# PCB-Main.net
KiCad netlist of a schematic drawn in EAGLE
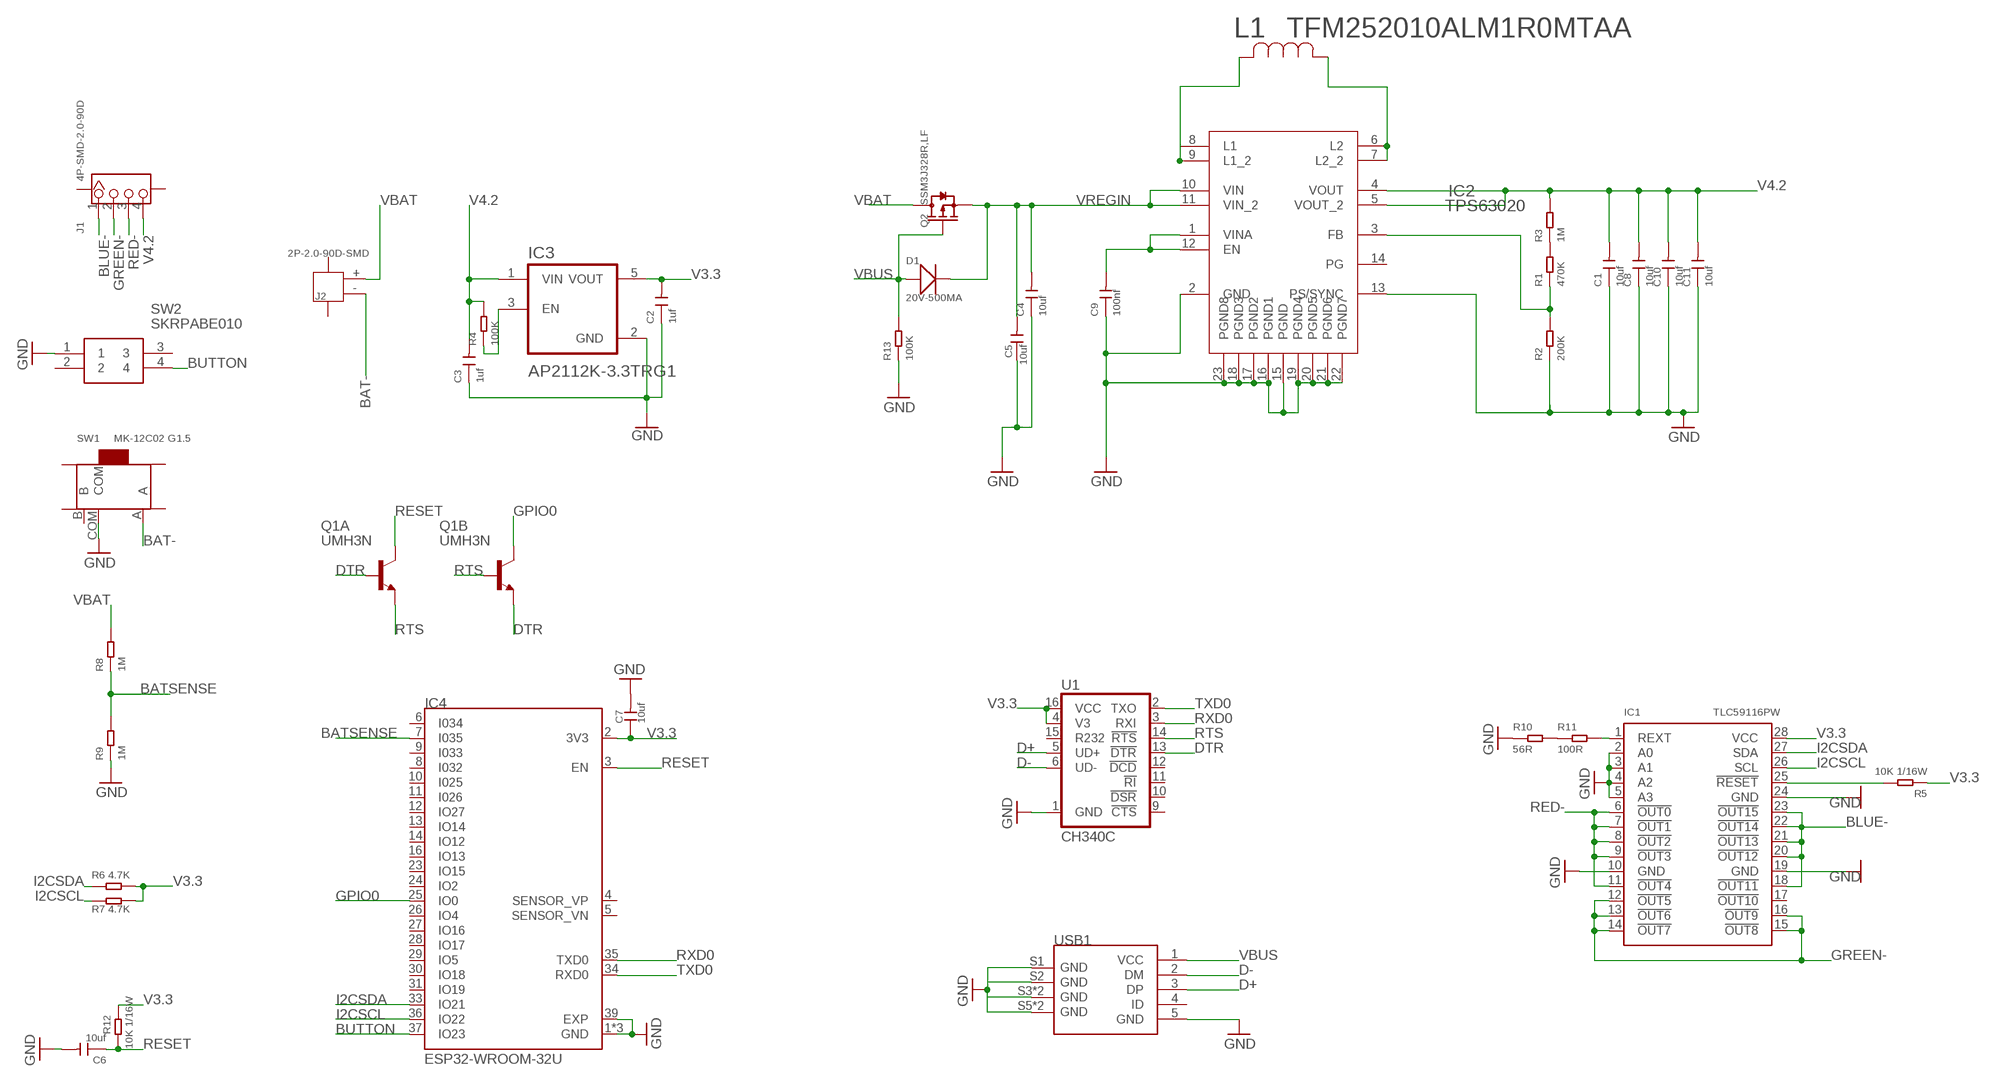
[diagram p0: schematic, sheet 1]

(export (version "E")
  (design (tool "Eeschema 10.0.6"))
  (components
    (comp (ref "C1")
      (value "10uf")
      (footprint "eagle-import:C0402")
      (fields (field (name "MPN") "CC0402MRX5R5BB106"))
      (libsource (lib "eagle-import") (part "CERAMIC-10UF-6.3V-20%-X5R(0402)"))
    )
    (comp (ref "C2")
      (value "1uf")
      (footprint "eagle-import:C0402")
      (fields (field (name "MPN") "CC0402KRX5R6BB105"))
      (libsource (lib "eagle-import") (part "CERAMIC-1UF-10V-10%-X5R(0402)"))
    )
    (comp (ref "C3")
      (value "1uf")
      (footprint "eagle-import:C0402")
      (fields (field (name "MPN") "CC0402KRX5R6BB105"))
      (libsource (lib "eagle-import") (part "CERAMIC-1UF-10V-10%-X5R(0402)"))
    )
    (comp (ref "C4")
      (value "10uf")
      (footprint "eagle-import:C0402")
      (fields (field (name "MPN") "CC0402MRX5R5BB106"))
      (libsource (lib "eagle-import") (part "CERAMIC-10UF-6.3V-20%-X5R(0402)"))
    )
    (comp (ref "C5")
      (value "10uf")
      (footprint "eagle-import:C0402")
      (fields (field (name "MPN") "CC0402MRX5R5BB106"))
      (libsource (lib "eagle-import") (part "CERAMIC-10UF-6.3V-20%-X5R(0402)"))
    )
    (comp (ref "C6")
      (value "10uf")
      (footprint "eagle-import:C0402")
      (fields (field (name "MPN") "CC0402MRX5R5BB106"))
      (libsource (lib "eagle-import") (part "CERAMIC-10UF-6.3V-20%-X5R(0402)"))
    )
    (comp (ref "C7")
      (value "10uf")
      (footprint "eagle-import:C0402")
      (fields (field (name "MPN") "CC0402MRX5R5BB106"))
      (libsource (lib "eagle-import") (part "CERAMIC-10UF-6.3V-20%-X5R(0402)"))
    )
    (comp (ref "C8")
      (value "10uf")
      (footprint "eagle-import:C0402")
      (fields (field (name "MPN") "CC0402MRX5R5BB106"))
      (libsource (lib "eagle-import") (part "CERAMIC-10UF-6.3V-20%-X5R(0402)"))
    )
    (comp (ref "C9")
      (value "100nf")
      (footprint "eagle-import:C0402")
      (fields (field (name "MPN") "CC0402KRX7R8BB104"))
      (libsource (lib "eagle-import") (part "CERAMIC-100NF-25V-10%-X7R(0402)"))
    )
    (comp (ref "C10")
      (value "10uf")
      (footprint "eagle-import:C0402")
      (fields (field (name "MPN") "CC0402MRX5R5BB106"))
      (libsource (lib "eagle-import") (part "CERAMIC-10UF-6.3V-20%-X5R(0402)"))
    )
    (comp (ref "C11")
      (value "10uf")
      (footprint "eagle-import:C0402")
      (fields (field (name "MPN") "CC0402MRX5R5BB106"))
      (libsource (lib "eagle-import") (part "CERAMIC-10UF-6.3V-20%-X5R(0402)"))
    )
    (comp (ref "D1")
      (value "20V-500MA")
      (footprint "eagle-import:SOD-123")
      (fields (field (name "MPN") "SS0520-7-F"))
      (libsource (lib "eagle-import") (part "SMD-DIODE-SCHOTTKY-20V-500MA(SOD-123)"))
    )
    (comp (ref "IC1")
      (value "TLC59116PW")
      (footprint "eagle-import:PW_R-PDSO-G28")
      (fields (field (name "MPN") "TLC59116IPWR"))
      (libsource (lib "eagle-import") (part "TLC59116PW"))
    )
    (comp (ref "IC2")
      (value "TPS63020")
      (footprint "eagle-import:QFN14-3X4MM")
      (fields (field (name "MF") "Texas Instruments") (field (name "MPN") "TPS63020DSJR"))
      (libsource (lib "eagle-import") (part "TPS63020"))
    )
    (comp (ref "IC3")
      (value "AP2112K-3.3TRG1")
      (footprint "eagle-import:SOT95P285X140-5N")
      (fields (field (name "MF") "Diodes Inc."))
      (libsource (lib "eagle-import") (part "AP2112K-3.3TRG1"))
    )
    (comp (ref "IC4")
      (value "ESP32-WROOM-32U")
      (footprint "eagle-import:XCVR_ESP32-WROOM-32U")
      (fields (field (name "MF") "Espressif Systems"))
      (libsource (lib "eagle-import") (part "ESP32-WROOM-32UNOSD"))
    )
    (comp (ref "J1")
      (value "4P-SMD-2.0-90D")
      (footprint "eagle-import:HW4-SMD-2.0-90D")
      (libsource (lib "eagle-import") (part "GROVE-CONNECTOR-SMD-90D(4+2P-2.0)"))
    )
    (comp (ref "J2")
      (value "2P-2.0-90D-SMD")
      (footprint "eagle-import:HW2-SMD-2.0-90D")
      (libsource (lib "eagle-import") (part "CONN-HEADER-SMD-PH-SIDE-(2P-2.0MM)"))
    )
    (comp (ref "L1")
      (value "TFM252010ALM1R0MTAA")
      (footprint "eagle-import:IND_1008")
      (libsource (lib "eagle-import") (part "TFM252010ALM1R0MTAA"))
    )
    (comp (ref "Q1")
      (value "UMH3N")
      (footprint "eagle-import:UMT6")
      (fields (field (name "MPN") "UMH3NTN"))
      (libsource (lib "eagle-import") (part "UMH3N"))
    )
    (comp (ref "Q2")
      (value "SSM3J328R,LF")
      (footprint "eagle-import:SOT-23")
      (libsource (lib "eagle-import") (part "SMD-MOSFET-P-CH-20V-6A-SSM3J328R(SOT-23)"))
    )
    (comp (ref "R1")
      (value "470K")
      (footprint "eagle-import:R0402")
      (fields (field (name "MPN") "RC0402FR-07470KL"))
      (libsource (lib "eagle-import") (part "SMD-RES-470K-1%-1/16W(0402)"))
    )
    (comp (ref "R2")
      (value "200K")
      (footprint "eagle-import:R0402")
      (fields (field (name "MPN") "RC0402JR-070RL"))
      (libsource (lib "eagle-import") (part "SMD-RES-200K-5%-1/16W(0402)"))
    )
    (comp (ref "R3")
      (value "1M")
      (footprint "eagle-import:R0402")
      (fields (field (name "MPN") "RC0402FR-071ML"))
      (libsource (lib "eagle-import") (part "SMD-RES-1M-1%-1/16W(0402)"))
    )
    (comp (ref "R4")
      (value "100K")
      (footprint "eagle-import:R0402")
      (fields (field (name "MPN") "RC0402FR-07100KL"))
      (libsource (lib "eagle-import") (part "SMD-RES-100K-1%-1/16W(0402)"))
    )
    (comp (ref "R5")
      (value "10K 1/16W")
      (footprint "eagle-import:R0402")
      (fields (field (name "MPN") "RC0402FR-0710KL"))
      (libsource (lib "eagle-import") (part "SMD-RES-10K-1%-1/16W(0402)"))
    )
    (comp (ref "R6")
      (value "4.7K")
      (footprint "eagle-import:R0402")
      (fields (field (name "MPN") "RC0402JR-074K7L"))
      (libsource (lib "eagle-import") (part "SMD-RES-4.7K-5%-1/16W(0402)"))
    )
    (comp (ref "R7")
      (value "4.7K")
      (footprint "eagle-import:R0402")
      (fields (field (name "MPN") "RC0402JR-074K7L"))
      (libsource (lib "eagle-import") (part "SMD-RES-4.7K-5%-1/16W(0402)"))
    )
    (comp (ref "R8")
      (value "1M")
      (footprint "eagle-import:R0402")
      (fields (field (name "MPN") "RC0402FR-071ML"))
      (libsource (lib "eagle-import") (part "SMD-RES-1M-1%-1/16W(0402)"))
    )
    (comp (ref "R9")
      (value "1M")
      (footprint "eagle-import:R0402")
      (fields (field (name "MPN") "RC0402FR-071ML"))
      (libsource (lib "eagle-import") (part "SMD-RES-1M-1%-1/16W(0402)"))
    )
    (comp (ref "R10")
      (value "56R")
      (footprint "eagle-import:R0402")
      (fields (field (name "MPN") "RC0402FR-0756RL"))
      (libsource (lib "eagle-import") (part "SMD-RES-56Ω-1%-1/16W(0402)"))
    )
    (comp (ref "R11")
      (value "100R")
      (footprint "eagle-import:R0402")
      (fields (field (name "MPN") "RC0402JR-07100RL"))
      (libsource (lib "eagle-import") (part "SMD-RES-100R-5%-1/16W(0402)"))
    )
    (comp (ref "R12")
      (value "10K 1/16W")
      (footprint "eagle-import:R0402")
      (fields (field (name "MPN") "RC0402FR-0710KL"))
      (libsource (lib "eagle-import") (part "SMD-RES-10K-1%-1/16W(0402)"))
    )
    (comp (ref "R13")
      (value "100K")
      (footprint "eagle-import:R0402")
      (fields (field (name "MPN") "RC0402FR-07100KL"))
      (libsource (lib "eagle-import") (part "SMD-RES-100K-1%-1/16W(0402)"))
    )
    (comp (ref "SW1")
      (value "MK-12C02 G1.5")
      (footprint "eagle-import:SW7-SMD-L6.7X2.7X3.2MM")
      (libsource (lib "eagle-import") (part "SMD-TOGGLE-SWITCH-ON-ON(3+4P-6.7X2.7MM)"))
    )
    (comp (ref "SW2")
      (value "SKRPABE010")
      (footprint "eagle-import:SMT(4.2X3.2)")
      (fields (field (name "MOUSER_PART_NUMBER") "688-SKRPAB") (field (name "RS_PART_NUMBER") "9174087"))
      (libsource (lib "eagle-import") (part "SKRPABE010"))
    )
    (comp (ref "U1")
      (value "CH340C")
      (footprint "eagle-import:SO016")
      (libsource (lib "eagle-import") (part "CH340C"))
    )
    (comp (ref "USB1")
      (value "10118193-0001LF")
      (footprint "eagle-import:MICRO-USB5+6P-SMD-0.65-B")
      (libsource (lib "eagle-import") (part "MICRO-USB-SMD-B-(10118193-0001LF)"))
    )
  )
  (nets
    (net (code "1") (name "/BAT-") (class "Default")
      (node (ref "J2") (pin "-") (pinfunction "2_-") (pintype "bidirectional"))
      (node (ref "SW1") (pin "A") (pinfunction "A_A") (pintype "bidirectional"))
    )
    (net (code "2") (name "/BATSENSE") (class "Default")
      (node (ref "IC4") (pin "7") (pinfunction "I035_7") (pintype "input"))
      (node (ref "R8") (pin "1") (pinfunction "1_1") (pintype "passive"))
      (node (ref "R9") (pin "2") (pinfunction "2_2") (pintype "passive"))
    )
    (net (code "3") (name "/BLUE-") (class "Default")
      (node (ref "IC1") (pin "18") (pinfunction "~{OUT11}_18") (pintype "bidirectional"))
      (node (ref "IC1") (pin "20") (pinfunction "~{OUT12}_20") (pintype "bidirectional"))
      (node (ref "IC1") (pin "21") (pinfunction "~{OUT13}_21") (pintype "bidirectional"))
      (node (ref "IC1") (pin "22") (pinfunction "~{OUT14}_22") (pintype "bidirectional"))
      (node (ref "IC1") (pin "23") (pinfunction "~{OUT15}_23") (pintype "bidirectional"))
      (node (ref "J1") (pin "1") (pinfunction "1_1") (pintype "bidirectional"))
    )
    (net (code "4") (name "/BUTTON") (class "Default")
      (node (ref "IC4") (pin "37") (pinfunction "IO23_37") (pintype "bidirectional"))
      (node (ref "SW2") (pin "4") (pinfunction "4_4") (pintype "bidirectional"))
    )
    (net (code "5") (name "/D+") (class "Default")
      (node (ref "U1") (pin "5") (pinfunction "UD+_5") (pintype "bidirectional"))
      (node (ref "USB1") (pin "3") (pinfunction "DP_3") (pintype "bidirectional"))
    )
    (net (code "6") (name "/D-") (class "Default")
      (node (ref "U1") (pin "6") (pinfunction "UD-_6") (pintype "bidirectional"))
      (node (ref "USB1") (pin "2") (pinfunction "DM_2") (pintype "bidirectional"))
    )
    (net (code "7") (name "/DTR") (class "Default")
      (node (ref "Q1") (pin "2") (pinfunction "B_2") (pintype "passive"))
      (node (ref "Q1") (pin "4") (pinfunction "E_4") (pintype "passive"))
      (node (ref "U1") (pin "13") (pinfunction "~{DTR}_13") (pintype "bidirectional"))
    )
    (net (code "8") (name "/GPIO0") (class "Default")
      (node (ref "IC4") (pin "25") (pinfunction "IO0_25") (pintype "bidirectional"))
      (node (ref "Q1") (pin "3") (pinfunction "C_3") (pintype "passive"))
    )
    (net (code "9") (name "/GREEN-") (class "Default")
      (node (ref "IC1") (pin "12") (pinfunction "~{OUT5}_12") (pintype "bidirectional"))
      (node (ref "IC1") (pin "13") (pinfunction "~{OUT6}_13") (pintype "bidirectional"))
      (node (ref "IC1") (pin "14") (pinfunction "~{OUT7}_14") (pintype "bidirectional"))
      (node (ref "IC1") (pin "15") (pinfunction "~{OUT8}_15") (pintype "bidirectional"))
      (node (ref "IC1") (pin "16") (pinfunction "~{OUT9}_16") (pintype "bidirectional"))
      (node (ref "J1") (pin "2") (pinfunction "2_2") (pintype "bidirectional"))
    )
    (net (code "10") (name "/I2CSCL") (class "Default")
      (node (ref "IC1") (pin "26") (pinfunction "SCL_26") (pintype "bidirectional"))
      (node (ref "IC4") (pin "36") (pinfunction "IO22_36") (pintype "bidirectional"))
      (node (ref "R7") (pin "1") (pinfunction "1_1") (pintype "passive"))
    )
    (net (code "11") (name "/I2CSDA") (class "Default")
      (node (ref "IC1") (pin "27") (pinfunction "SDA_27") (pintype "bidirectional"))
      (node (ref "IC4") (pin "33") (pinfunction "IO21_33") (pintype "bidirectional"))
      (node (ref "R6") (pin "1") (pinfunction "1_1") (pintype "passive"))
    )
    (net (code "12") (name "/RED-") (class "Default")
      (node (ref "IC1") (pin "11") (pinfunction "~{OUT4}_11") (pintype "bidirectional"))
      (node (ref "IC1") (pin "6") (pinfunction "~{OUT0}_6") (pintype "bidirectional"))
      (node (ref "IC1") (pin "7") (pinfunction "~{OUT1}_7") (pintype "bidirectional"))
      (node (ref "IC1") (pin "8") (pinfunction "~{OUT2}_8") (pintype "bidirectional"))
      (node (ref "IC1") (pin "9") (pinfunction "~{OUT3}_9") (pintype "bidirectional"))
      (node (ref "J1") (pin "3") (pinfunction "3_3") (pintype "bidirectional"))
    )
    (net (code "13") (name "/RESET") (class "Default")
      (node (ref "C6") (pin "1") (pinfunction "1_1") (pintype "passive"))
      (node (ref "IC4") (pin "3") (pinfunction "EN_3") (pintype "input"))
      (node (ref "Q1") (pin "6") (pinfunction "C_6") (pintype "passive"))
      (node (ref "R12") (pin "1") (pinfunction "1_1") (pintype "passive"))
    )
    (net (code "14") (name "/RTS") (class "Default")
      (node (ref "Q1") (pin "1") (pinfunction "E_1") (pintype "passive"))
      (node (ref "Q1") (pin "5") (pinfunction "B_5") (pintype "passive"))
      (node (ref "U1") (pin "14") (pinfunction "~{RTS}_14") (pintype "bidirectional"))
    )
    (net (code "15") (name "/RXD0") (class "Default")
      (node (ref "IC4") (pin "35") (pinfunction "TXD0_35") (pintype "bidirectional"))
      (node (ref "U1") (pin "3") (pinfunction "RXI_3") (pintype "bidirectional"))
    )
    (net (code "16") (name "/TXD0") (class "Default")
      (node (ref "IC4") (pin "34") (pinfunction "RXD0_34") (pintype "bidirectional"))
      (node (ref "U1") (pin "2") (pinfunction "TXO_2") (pintype "bidirectional"))
    )
    (net (code "17") (name "/V3.3") (class "Default")
      (node (ref "C2") (pin "2") (pinfunction "2_2") (pintype "passive"))
      (node (ref "C7") (pin "1") (pinfunction "1_1") (pintype "passive"))
      (node (ref "IC1") (pin "28") (pinfunction "VCC_28") (pintype "bidirectional"))
      (node (ref "IC3") (pin "5") (pinfunction "VOUT_5") (pintype "power_in"))
      (node (ref "IC4") (pin "2") (pinfunction "3V3_2") (pintype "power_in"))
      (node (ref "R12") (pin "2") (pinfunction "2_2") (pintype "passive"))
      (node (ref "R5") (pin "1") (pinfunction "1_1") (pintype "passive"))
      (node (ref "R6") (pin "2") (pinfunction "2_2") (pintype "passive"))
      (node (ref "R7") (pin "2") (pinfunction "2_2") (pintype "passive"))
      (node (ref "U1") (pin "16") (pinfunction "VCC_16") (pintype "bidirectional"))
      (node (ref "U1") (pin "4") (pinfunction "V3_4") (pintype "bidirectional"))
    )
    (net (code "18") (name "/V4.2") (class "Default")
      (node (ref "C1") (pin "2") (pinfunction "2_2") (pintype "passive"))
      (node (ref "C10") (pin "2") (pinfunction "2_2") (pintype "passive"))
      (node (ref "C11") (pin "2") (pinfunction "2_2") (pintype "passive"))
      (node (ref "C3") (pin "2") (pinfunction "2_2") (pintype "passive"))
      (node (ref "C8") (pin "2") (pinfunction "2_2") (pintype "passive"))
      (node (ref "IC2") (pin "4") (pinfunction "VOUT_4") (pintype "bidirectional"))
      (node (ref "IC2") (pin "5") (pinfunction "VOUT_2_5") (pintype "bidirectional"))
      (node (ref "IC3") (pin "1") (pinfunction "VIN_1") (pintype "power_in"))
      (node (ref "J1") (pin "4") (pinfunction "4_4") (pintype "bidirectional"))
      (node (ref "R3") (pin "2") (pinfunction "2_2") (pintype "passive"))
      (node (ref "R4") (pin "2") (pinfunction "2_2") (pintype "passive"))
    )
    (net (code "19") (name "/VBAT") (class "Default")
      (node (ref "J2") (pin "+") (pinfunction "1_+") (pintype "bidirectional"))
      (node (ref "Q2") (pin "3") (pinfunction "D_3") (pintype "passive"))
      (node (ref "R8") (pin "2") (pinfunction "2_2") (pintype "passive"))
    )
    (net (code "20") (name "/VBUS") (class "Default")
      (node (ref "D1") (pin "+") (pinfunction "+_+") (pintype "passive"))
      (node (ref "Q2") (pin "1") (pinfunction "G_1") (pintype "passive"))
      (node (ref "R13") (pin "2") (pinfunction "2_2") (pintype "passive"))
      (node (ref "USB1") (pin "1") (pinfunction "VCC_1") (pintype "bidirectional"))
    )
    (net (code "21") (name "/VREGIN") (class "Default")
      (node (ref "C4") (pin "2") (pinfunction "2_2") (pintype "passive"))
      (node (ref "C5") (pin "2") (pinfunction "2_2") (pintype "passive"))
      (node (ref "D1") (pin "-") (pinfunction "-_-") (pintype "passive"))
      (node (ref "IC2") (pin "10") (pinfunction "VIN_10") (pintype "bidirectional"))
      (node (ref "IC2") (pin "11") (pinfunction "VIN_2_11") (pintype "bidirectional"))
      (node (ref "Q2") (pin "2") (pinfunction "S_2") (pintype "passive"))
    )
    (net (code "22") (name "GND") (class "Default")
      (node (ref "C1") (pin "1") (pinfunction "1_1") (pintype "passive"))
      (node (ref "C10") (pin "1") (pinfunction "1_1") (pintype "passive"))
      (node (ref "C11") (pin "1") (pinfunction "1_1") (pintype "passive"))
      (node (ref "C2") (pin "1") (pinfunction "1_1") (pintype "passive"))
      (node (ref "C3") (pin "1") (pinfunction "1_1") (pintype "passive"))
      (node (ref "C4") (pin "1") (pinfunction "1_1") (pintype "passive"))
      (node (ref "C5") (pin "1") (pinfunction "1_1") (pintype "passive"))
      (node (ref "C6") (pin "2") (pinfunction "2_2") (pintype "passive"))
      (node (ref "C7") (pin "2") (pinfunction "2_2") (pintype "passive"))
      (node (ref "C8") (pin "1") (pinfunction "1_1") (pintype "passive"))
      (node (ref "C9") (pin "1") (pinfunction "1_1") (pintype "passive"))
      (node (ref "IC1") (pin "10") (pinfunction "GND_10") (pintype "bidirectional"))
      (node (ref "IC1") (pin "19") (pinfunction "GND_19") (pintype "bidirectional"))
      (node (ref "IC1") (pin "2") (pinfunction "A0_2") (pintype "bidirectional"))
      (node (ref "IC1") (pin "24") (pinfunction "GND_24") (pintype "bidirectional"))
      (node (ref "IC1") (pin "3") (pinfunction "A1_3") (pintype "bidirectional"))
      (node (ref "IC1") (pin "4") (pinfunction "A2_4") (pintype "bidirectional"))
      (node (ref "IC1") (pin "5") (pinfunction "A3_5") (pintype "bidirectional"))
      (node (ref "IC2") (pin "13") (pinfunction "PS/SYNC_13") (pintype "bidirectional"))
      (node (ref "IC2") (pin "15") (pinfunction "PGND_15") (pintype "bidirectional"))
      (node (ref "IC2") (pin "16") (pinfunction "PGND1_16") (pintype "bidirectional"))
      (node (ref "IC2") (pin "17") (pinfunction "PGND2_17") (pintype "bidirectional"))
      (node (ref "IC2") (pin "18") (pinfunction "PGND3_18") (pintype "bidirectional"))
      (node (ref "IC2") (pin "19") (pinfunction "PGND4_19") (pintype "bidirectional"))
      (node (ref "IC2") (pin "2") (pinfunction "GND_2") (pintype "bidirectional"))
      (node (ref "IC2") (pin "20") (pinfunction "PGND5_20") (pintype "bidirectional"))
      (node (ref "IC2") (pin "21") (pinfunction "PGND6_21") (pintype "bidirectional"))
      (node (ref "IC2") (pin "22") (pinfunction "PGND7_22") (pintype "bidirectional"))
      (node (ref "IC2") (pin "23") (pinfunction "PGND8_23") (pintype "bidirectional"))
      (node (ref "IC3") (pin "2") (pinfunction "GND_2") (pintype "power_in"))
      (node (ref "IC4") (pin "1") (pinfunction "GND_1") (pintype "power_in"))
      (node (ref "IC4") (pin "15") (pinfunction "GND_15") (pintype "power_in"))
      (node (ref "IC4") (pin "38") (pinfunction "GND_38") (pintype "power_in"))
      (node (ref "IC4") (pin "39") (pinfunction "EXP_39") (pintype "power_in"))
      (node (ref "R10") (pin "1") (pinfunction "1_1") (pintype "passive"))
      (node (ref "R13") (pin "1") (pinfunction "1_1") (pintype "passive"))
      (node (ref "R2") (pin "1") (pinfunction "1_1") (pintype "passive"))
      (node (ref "R9") (pin "1") (pinfunction "1_1") (pintype "passive"))
      (node (ref "SW1") (pin "COM") (pinfunction "COM_COM") (pintype "bidirectional"))
      (node (ref "SW2") (pin "1") (pinfunction "1_1") (pintype "bidirectional"))
      (node (ref "U1") (pin "1") (pinfunction "GND_1") (pintype "bidirectional"))
      (node (ref "USB1") (pin "5") (pinfunction "GND_5") (pintype "bidirectional"))
      (node (ref "USB1") (pin "S1") (pinfunction "GND_S1") (pintype "bidirectional"))
      (node (ref "USB1") (pin "S2") (pinfunction "GND_S2") (pintype "bidirectional"))
      (node (ref "USB1") (pin "S3") (pinfunction "GND_S3") (pintype "bidirectional"))
      (node (ref "USB1") (pin "S4") (pinfunction "GND_S4") (pintype "bidirectional"))
      (node (ref "USB1") (pin "S5") (pinfunction "GND_S5") (pintype "bidirectional"))
      (node (ref "USB1") (pin "S6") (pinfunction "GND_S6") (pintype "bidirectional"))
    )
    (net (code "23") (name "Net-(IC1-REXT)") (class "Default")
      (node (ref "IC1") (pin "1") (pinfunction "REXT_1") (pintype "bidirectional"))
      (node (ref "R11") (pin "2") (pinfunction "2_2") (pintype "passive"))
    )
    (net (code "24") (name "Net-(IC1-~{RESET})") (class "Default")
      (node (ref "IC1") (pin "25") (pinfunction "~{RESET}_25") (pintype "bidirectional"))
      (node (ref "R5") (pin "2") (pinfunction "2_2") (pintype "passive"))
    )
    (net (code "25") (name "Net-(IC2-EN)") (class "Default")
      (node (ref "C9") (pin "2") (pinfunction "2_2") (pintype "passive"))
      (node (ref "IC2") (pin "1") (pinfunction "VINA_1") (pintype "bidirectional"))
      (node (ref "IC2") (pin "12") (pinfunction "EN_12") (pintype "bidirectional"))
    )
    (net (code "26") (name "Net-(IC2-FB)") (class "Default")
      (node (ref "IC2") (pin "3") (pinfunction "FB_3") (pintype "bidirectional"))
      (node (ref "R1") (pin "1") (pinfunction "1_1") (pintype "passive"))
      (node (ref "R2") (pin "2") (pinfunction "2_2") (pintype "passive"))
    )
    (net (code "27") (name "Net-(IC2-L1)") (class "Default")
      (node (ref "IC2") (pin "8") (pinfunction "L1_8") (pintype "bidirectional"))
      (node (ref "IC2") (pin "9") (pinfunction "L1_2_9") (pintype "bidirectional"))
      (node (ref "L1") (pin "2") (pinfunction "2_2") (pintype "passive"))
    )
    (net (code "28") (name "Net-(IC2-L2)") (class "Default")
      (node (ref "IC2") (pin "6") (pinfunction "L2_6") (pintype "bidirectional"))
      (node (ref "IC2") (pin "7") (pinfunction "L2_2_7") (pintype "bidirectional"))
      (node (ref "L1") (pin "1") (pinfunction "1_1") (pintype "passive"))
    )
    (net (code "29") (name "Net-(IC3-EN)") (class "Default")
      (node (ref "IC3") (pin "3") (pinfunction "EN_3") (pintype "input"))
      (node (ref "R4") (pin "1") (pinfunction "1_1") (pintype "passive"))
    )
    (net (code "30") (name "Net-(R1-Pad2)") (class "Default")
      (node (ref "R1") (pin "2") (pinfunction "2_2") (pintype "passive"))
      (node (ref "R3") (pin "1") (pinfunction "1_1") (pintype "passive"))
    )
    (net (code "31") (name "Net-(R10-Pad2)") (class "Default")
      (node (ref "R10") (pin "2") (pinfunction "2_2") (pintype "passive"))
      (node (ref "R11") (pin "1") (pinfunction "1_1") (pintype "passive"))
    )
    (net (code "32") (name "unconnected-(IC1-~{OUT10}-Pad17)") (class "Default")
      (node (ref "IC1") (pin "17") (pinfunction "~{OUT10}_17") (pintype "bidirectional"))
    )
    (net (code "33") (name "unconnected-(IC2-PG-Pad14)") (class "Default")
      (node (ref "IC2") (pin "14") (pinfunction "PG_14") (pintype "bidirectional"))
    )
    (net (code "34") (name "unconnected-(IC4-I025-Pad10)") (class "Default")
      (node (ref "IC4") (pin "10") (pinfunction "I025_10") (pintype "bidirectional"))
    )
    (net (code "35") (name "unconnected-(IC4-I026-Pad11)") (class "Default")
      (node (ref "IC4") (pin "11") (pinfunction "I026_11") (pintype "bidirectional"))
    )
    (net (code "36") (name "unconnected-(IC4-I032-Pad8)") (class "Default")
      (node (ref "IC4") (pin "8") (pinfunction "I032_8") (pintype "bidirectional"))
    )
    (net (code "37") (name "unconnected-(IC4-I033-Pad9)") (class "Default")
      (node (ref "IC4") (pin "9") (pinfunction "I033_9") (pintype "bidirectional"))
    )
    (net (code "38") (name "unconnected-(IC4-I034-Pad6)") (class "Default")
      (node (ref "IC4") (pin "6") (pinfunction "I034_6") (pintype "input"))
    )
    (net (code "39") (name "unconnected-(IC4-IO2-Pad24)") (class "Default")
      (node (ref "IC4") (pin "24") (pinfunction "IO2_24") (pintype "bidirectional"))
    )
    (net (code "40") (name "unconnected-(IC4-IO4-Pad26)") (class "Default")
      (node (ref "IC4") (pin "26") (pinfunction "IO4_26") (pintype "bidirectional"))
    )
    (net (code "41") (name "unconnected-(IC4-IO5-Pad29)") (class "Default")
      (node (ref "IC4") (pin "29") (pinfunction "IO5_29") (pintype "bidirectional"))
    )
    (net (code "42") (name "unconnected-(IC4-IO12-Pad14)") (class "Default")
      (node (ref "IC4") (pin "14") (pinfunction "IO12_14") (pintype "bidirectional"))
    )
    (net (code "43") (name "unconnected-(IC4-IO13-Pad16)") (class "Default")
      (node (ref "IC4") (pin "16") (pinfunction "IO13_16") (pintype "bidirectional"))
    )
    (net (code "44") (name "unconnected-(IC4-IO14-Pad13)") (class "Default")
      (node (ref "IC4") (pin "13") (pinfunction "IO14_13") (pintype "bidirectional"))
    )
    (net (code "45") (name "unconnected-(IC4-IO15-Pad23)") (class "Default")
      (node (ref "IC4") (pin "23") (pinfunction "IO15_23") (pintype "bidirectional"))
    )
    (net (code "46") (name "unconnected-(IC4-IO16-Pad27)") (class "Default")
      (node (ref "IC4") (pin "27") (pinfunction "IO16_27") (pintype "bidirectional"))
    )
    (net (code "47") (name "unconnected-(IC4-IO17-Pad28)") (class "Default")
      (node (ref "IC4") (pin "28") (pinfunction "IO17_28") (pintype "bidirectional"))
    )
    (net (code "48") (name "unconnected-(IC4-IO18-Pad30)") (class "Default")
      (node (ref "IC4") (pin "30") (pinfunction "IO18_30") (pintype "bidirectional"))
    )
    (net (code "49") (name "unconnected-(IC4-IO19-Pad31)") (class "Default")
      (node (ref "IC4") (pin "31") (pinfunction "IO19_31") (pintype "bidirectional"))
    )
    (net (code "50") (name "unconnected-(IC4-IO27-Pad12)") (class "Default")
      (node (ref "IC4") (pin "12") (pinfunction "IO27_12") (pintype "bidirectional"))
    )
    (net (code "51") (name "unconnected-(IC4-SENSOR_VN-Pad5)") (class "Default")
      (node (ref "IC4") (pin "5") (pinfunction "SENSOR_VN_5") (pintype "input"))
    )
    (net (code "52") (name "unconnected-(IC4-SENSOR_VP-Pad4)") (class "Default")
      (node (ref "IC4") (pin "4") (pinfunction "SENSOR_VP_4") (pintype "input"))
    )
    (net (code "53") (name "unconnected-(J1-PadSS1)") (class "Default")
      (node (ref "J1") (pin "SS1") (pinfunction "SS1_SS1") (pintype "bidirectional"))
    )
    (net (code "54") (name "unconnected-(J1-PadSS2)") (class "Default")
      (node (ref "J1") (pin "SS2") (pinfunction "SS2_SS2") (pintype "bidirectional"))
    )
    (net (code "55") (name "unconnected-(J2-Pad3)") (class "Default")
      (node (ref "J2") (pin "3") (pinfunction "3_3") (pintype "bidirectional"))
    )
    (net (code "56") (name "unconnected-(J2-Pad4)") (class "Default")
      (node (ref "J2") (pin "4") (pinfunction "4_4") (pintype "bidirectional"))
    )
    (net (code "57") (name "unconnected-(SW1-PadB)") (class "Default")
      (node (ref "SW1") (pin "B") (pinfunction "B_B") (pintype "bidirectional"))
    )
    (net (code "58") (name "unconnected-(SW1-PadSS1)") (class "Default")
      (node (ref "SW1") (pin "SS1") (pinfunction "SS1_SS1") (pintype "bidirectional"))
    )
    (net (code "59") (name "unconnected-(SW1-PadSS2)") (class "Default")
      (node (ref "SW1") (pin "SS2") (pinfunction "SS2_SS2") (pintype "bidirectional"))
    )
    (net (code "60") (name "unconnected-(SW1-PadSS3)") (class "Default")
      (node (ref "SW1") (pin "SS3") (pinfunction "SS3_SS3") (pintype "bidirectional"))
    )
    (net (code "61") (name "unconnected-(SW1-PadSS4)") (class "Default")
      (node (ref "SW1") (pin "SS4") (pinfunction "SS4_SS4") (pintype "bidirectional"))
    )
    (net (code "62") (name "unconnected-(SW2-Pad2)") (class "Default")
      (node (ref "SW2") (pin "2") (pinfunction "2_2") (pintype "bidirectional"))
    )
    (net (code "63") (name "unconnected-(SW2-Pad3)") (class "Default")
      (node (ref "SW2") (pin "3") (pinfunction "3_3") (pintype "bidirectional"))
    )
    (net (code "64") (name "unconnected-(U1-R232-Pad15)") (class "Default")
      (node (ref "U1") (pin "15") (pinfunction "R232_15") (pintype "bidirectional"))
    )
    (net (code "65") (name "unconnected-(U1-~{CTS}-Pad9)") (class "Default")
      (node (ref "U1") (pin "9") (pinfunction "~{CTS}_9") (pintype "bidirectional"))
    )
    (net (code "66") (name "unconnected-(U1-~{DCD}-Pad12)") (class "Default")
      (node (ref "U1") (pin "12") (pinfunction "~{DCD}_12") (pintype "bidirectional"))
    )
    (net (code "67") (name "unconnected-(U1-~{DSR}-Pad10)") (class "Default")
      (node (ref "U1") (pin "10") (pinfunction "~{DSR}_10") (pintype "bidirectional"))
    )
    (net (code "68") (name "unconnected-(U1-~{RI}-Pad11)") (class "Default")
      (node (ref "U1") (pin "11") (pinfunction "~{RI}_11") (pintype "bidirectional"))
    )
    (net (code "69") (name "unconnected-(USB1-ID-Pad4)") (class "Default")
      (node (ref "USB1") (pin "4") (pinfunction "ID_4") (pintype "bidirectional"))
    )
  )
)
